# Startgate_Controller_Daughterboard.net
KiCad netlist of a schematic drawn in EAGLE
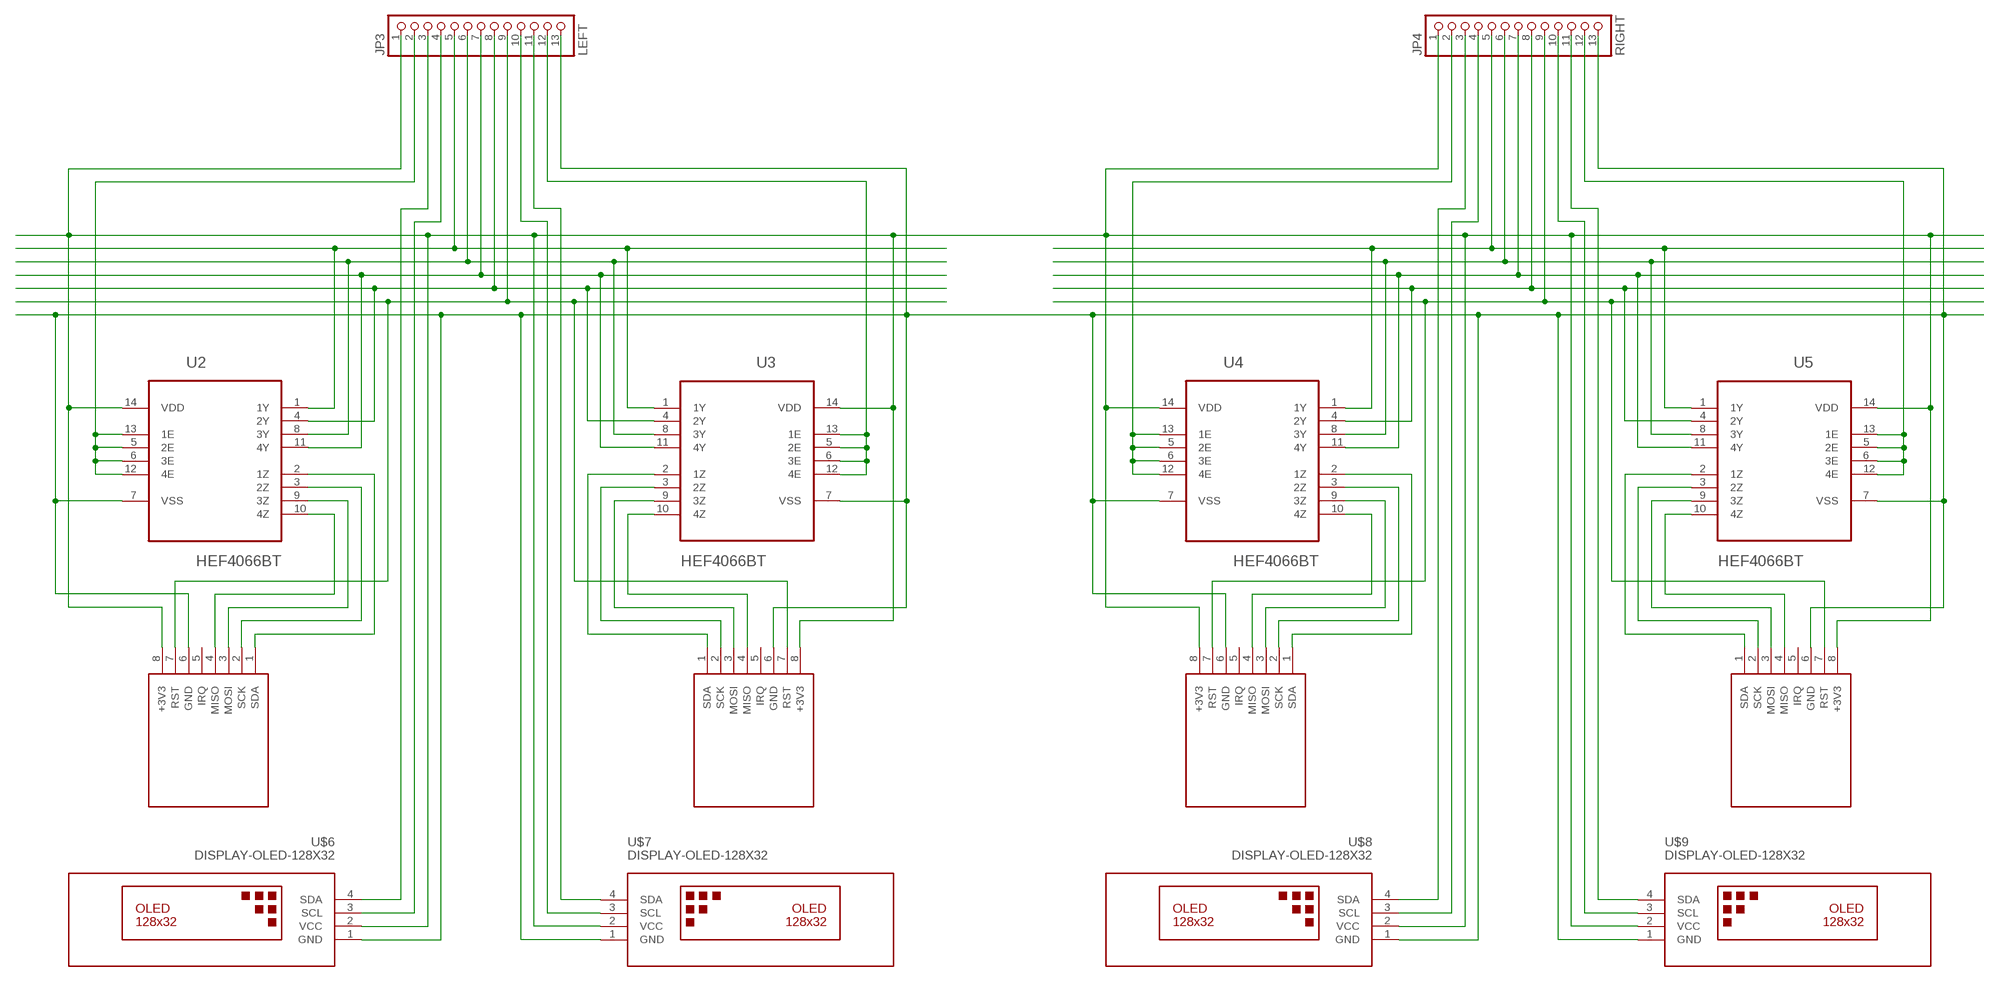
[diagram p0: schematic, sheet 1]

(export (version "E")
  (design (tool "Eeschema 10.0.6"))
  (components
    (comp (ref "JP3")
      (value "LEFT")
      (footprint "eagle-import:1X13")
      (libsource (lib "eagle-import") (part "PINHD-1X13"))
    )
    (comp (ref "JP4")
      (value "RIGHT")
      (footprint "eagle-import:1X13")
      (libsource (lib "eagle-import") (part "PINHD-1X13"))
    )
    (comp (ref "U$2")
      (value "RFID-RC522")
      (footprint "eagle-import:RFID-RC522")
      (libsource (lib "eagle-import") (part "RFID-RC522"))
    )
    (comp (ref "U$3")
      (value "RFID-RC522")
      (footprint "eagle-import:RFID-RC522")
      (libsource (lib "eagle-import") (part "RFID-RC522"))
    )
    (comp (ref "U$4")
      (value "RFID-RC522")
      (footprint "eagle-import:RFID-RC522")
      (libsource (lib "eagle-import") (part "RFID-RC522"))
    )
    (comp (ref "U$5")
      (value "RFID-RC522")
      (footprint "eagle-import:RFID-RC522")
      (libsource (lib "eagle-import") (part "RFID-RC522"))
    )
    (comp (ref "U$6")
      (value "DISPLAY-OLED-128X32")
      (footprint "eagle-import:DISPLAY-OLED-128X32")
      (libsource (lib "eagle-import") (part "DISPLAY-OLED-128X32"))
    )
    (comp (ref "U$7")
      (value "DISPLAY-OLED-128X32")
      (footprint "eagle-import:DISPLAY-OLED-128X32")
      (libsource (lib "eagle-import") (part "DISPLAY-OLED-128X32"))
    )
    (comp (ref "U$8")
      (value "DISPLAY-OLED-128X32")
      (footprint "eagle-import:DISPLAY-OLED-128X32")
      (libsource (lib "eagle-import") (part "DISPLAY-OLED-128X32"))
    )
    (comp (ref "U$9")
      (value "DISPLAY-OLED-128X32")
      (footprint "eagle-import:DISPLAY-OLED-128X32")
      (libsource (lib "eagle-import") (part "DISPLAY-OLED-128X32"))
    )
    (comp (ref "U2")
      (value "HEF4066BT")
      (footprint "eagle-import:SOIC127P600X175-14N")
      (libsource (lib "eagle-import") (part "HEF4066BT"))
    )
    (comp (ref "U3")
      (value "HEF4066BT")
      (footprint "eagle-import:SOIC127P600X175-14N")
      (libsource (lib "eagle-import") (part "HEF4066BT"))
    )
    (comp (ref "U4")
      (value "HEF4066BT")
      (footprint "eagle-import:SOIC127P600X175-14N")
      (libsource (lib "eagle-import") (part "HEF4066BT"))
    )
    (comp (ref "U5")
      (value "HEF4066BT")
      (footprint "eagle-import:SOIC127P600X175-14N")
      (libsource (lib "eagle-import") (part "HEF4066BT"))
    )
  )
  (nets
    (net (code "1") (name "/RST") (class "Default")
      (node (ref "JP3") (pin "9") (pinfunction "9_9") (pintype "passive"))
      (node (ref "JP4") (pin "9") (pinfunction "9_9") (pintype "passive"))
      (node (ref "U$2") (pin "7") (pinfunction "RST_7") (pintype "bidirectional"))
      (node (ref "U$3") (pin "7") (pinfunction "RST_7") (pintype "bidirectional"))
      (node (ref "U$4") (pin "7") (pinfunction "RST_7") (pintype "bidirectional"))
      (node (ref "U$5") (pin "7") (pinfunction "RST_7") (pintype "bidirectional"))
    )
    (net (code "2") (name "Net-(U$2-+3V3)") (class "Default")
      (node (ref "JP3") (pin "1") (pinfunction "1_1") (pintype "passive"))
      (node (ref "JP4") (pin "1") (pinfunction "1_1") (pintype "passive"))
      (node (ref "U$2") (pin "8") (pinfunction "+3V3_8") (pintype "power_in"))
      (node (ref "U$3") (pin "8") (pinfunction "+3V3_8") (pintype "power_in"))
      (node (ref "U$4") (pin "8") (pinfunction "+3V3_8") (pintype "power_in"))
      (node (ref "U$5") (pin "8") (pinfunction "+3V3_8") (pintype "power_in"))
      (node (ref "U$6") (pin "2") (pinfunction "VCC_2") (pintype "power_in"))
      (node (ref "U$7") (pin "2") (pinfunction "VCC_2") (pintype "power_in"))
      (node (ref "U$8") (pin "2") (pinfunction "VCC_2") (pintype "power_in"))
      (node (ref "U$9") (pin "2") (pinfunction "VCC_2") (pintype "power_in"))
      (node (ref "U2") (pin "14") (pinfunction "VDD_14") (pintype "power_in"))
      (node (ref "U3") (pin "14") (pinfunction "VDD_14") (pintype "power_in"))
      (node (ref "U4") (pin "14") (pinfunction "VDD_14") (pintype "power_in"))
      (node (ref "U5") (pin "14") (pinfunction "VDD_14") (pintype "power_in"))
    )
    (net (code "3") (name "Net-(U$2-GND)") (class "Default")
      (node (ref "JP3") (pin "13") (pinfunction "13_13") (pintype "passive"))
      (node (ref "JP4") (pin "13") (pinfunction "13_13") (pintype "passive"))
      (node (ref "U$2") (pin "6") (pinfunction "GND_6") (pintype "power_in"))
      (node (ref "U$3") (pin "6") (pinfunction "GND_6") (pintype "power_in"))
      (node (ref "U$4") (pin "6") (pinfunction "GND_6") (pintype "power_in"))
      (node (ref "U$5") (pin "6") (pinfunction "GND_6") (pintype "power_in"))
      (node (ref "U$6") (pin "1") (pinfunction "GND_1") (pintype "power_in"))
      (node (ref "U$7") (pin "1") (pinfunction "GND_1") (pintype "power_in"))
      (node (ref "U$8") (pin "1") (pinfunction "GND_1") (pintype "power_in"))
      (node (ref "U$9") (pin "1") (pinfunction "GND_1") (pintype "power_in"))
      (node (ref "U2") (pin "7") (pinfunction "VSS_7") (pintype "passive"))
      (node (ref "U3") (pin "7") (pinfunction "VSS_7") (pintype "passive"))
      (node (ref "U4") (pin "7") (pinfunction "VSS_7") (pintype "passive"))
      (node (ref "U5") (pin "7") (pinfunction "VSS_7") (pintype "passive"))
    )
    (net (code "4") (name "Net-(U$2-MISO)") (class "Default")
      (node (ref "U$2") (pin "4") (pinfunction "MISO_4") (pintype "bidirectional"))
      (node (ref "U2") (pin "10") (pinfunction "4Z_10") (pintype "bidirectional"))
    )
    (net (code "5") (name "Net-(U$2-MOSI)") (class "Default")
      (node (ref "U$2") (pin "3") (pinfunction "MOSI_3") (pintype "bidirectional"))
      (node (ref "U2") (pin "9") (pinfunction "3Z_9") (pintype "bidirectional"))
    )
    (net (code "6") (name "Net-(U$2-SCK)") (class "Default")
      (node (ref "U$2") (pin "2") (pinfunction "SCK_2") (pintype "bidirectional"))
      (node (ref "U2") (pin "3") (pinfunction "2Z_3") (pintype "bidirectional"))
    )
    (net (code "7") (name "Net-(U$2-SDA)") (class "Default")
      (node (ref "U$2") (pin "1") (pinfunction "SDA_1") (pintype "bidirectional"))
      (node (ref "U2") (pin "2") (pinfunction "1Z_2") (pintype "bidirectional"))
    )
    (net (code "8") (name "Net-(U$3-MISO)") (class "Default")
      (node (ref "U$3") (pin "4") (pinfunction "MISO_4") (pintype "bidirectional"))
      (node (ref "U3") (pin "10") (pinfunction "4Z_10") (pintype "bidirectional"))
    )
    (net (code "9") (name "Net-(U$3-MOSI)") (class "Default")
      (node (ref "U$3") (pin "3") (pinfunction "MOSI_3") (pintype "bidirectional"))
      (node (ref "U3") (pin "9") (pinfunction "3Z_9") (pintype "bidirectional"))
    )
    (net (code "10") (name "Net-(U$3-SCK)") (class "Default")
      (node (ref "U$3") (pin "2") (pinfunction "SCK_2") (pintype "bidirectional"))
      (node (ref "U3") (pin "3") (pinfunction "2Z_3") (pintype "bidirectional"))
    )
    (net (code "11") (name "Net-(U$3-SDA)") (class "Default")
      (node (ref "U$3") (pin "1") (pinfunction "SDA_1") (pintype "bidirectional"))
      (node (ref "U3") (pin "2") (pinfunction "1Z_2") (pintype "bidirectional"))
    )
    (net (code "12") (name "Net-(U$4-MISO)") (class "Default")
      (node (ref "U$4") (pin "4") (pinfunction "MISO_4") (pintype "bidirectional"))
      (node (ref "U4") (pin "10") (pinfunction "4Z_10") (pintype "bidirectional"))
    )
    (net (code "13") (name "Net-(U$4-MOSI)") (class "Default")
      (node (ref "U$4") (pin "3") (pinfunction "MOSI_3") (pintype "bidirectional"))
      (node (ref "U4") (pin "9") (pinfunction "3Z_9") (pintype "bidirectional"))
    )
    (net (code "14") (name "Net-(U$4-SCK)") (class "Default")
      (node (ref "U$4") (pin "2") (pinfunction "SCK_2") (pintype "bidirectional"))
      (node (ref "U4") (pin "3") (pinfunction "2Z_3") (pintype "bidirectional"))
    )
    (net (code "15") (name "Net-(U$4-SDA)") (class "Default")
      (node (ref "U$4") (pin "1") (pinfunction "SDA_1") (pintype "bidirectional"))
      (node (ref "U4") (pin "2") (pinfunction "1Z_2") (pintype "bidirectional"))
    )
    (net (code "16") (name "Net-(U$5-MISO)") (class "Default")
      (node (ref "U$5") (pin "4") (pinfunction "MISO_4") (pintype "bidirectional"))
      (node (ref "U5") (pin "10") (pinfunction "4Z_10") (pintype "bidirectional"))
    )
    (net (code "17") (name "Net-(U$5-MOSI)") (class "Default")
      (node (ref "U$5") (pin "3") (pinfunction "MOSI_3") (pintype "bidirectional"))
      (node (ref "U5") (pin "9") (pinfunction "3Z_9") (pintype "bidirectional"))
    )
    (net (code "18") (name "Net-(U$5-SCK)") (class "Default")
      (node (ref "U$5") (pin "2") (pinfunction "SCK_2") (pintype "bidirectional"))
      (node (ref "U5") (pin "3") (pinfunction "2Z_3") (pintype "bidirectional"))
    )
    (net (code "19") (name "Net-(U$5-SDA)") (class "Default")
      (node (ref "U$5") (pin "1") (pinfunction "SDA_1") (pintype "bidirectional"))
      (node (ref "U5") (pin "2") (pinfunction "1Z_2") (pintype "bidirectional"))
    )
    (net (code "20") (name "Net-(U$6-SCL)") (class "Default")
      (node (ref "JP3") (pin "4") (pinfunction "4_4") (pintype "passive"))
      (node (ref "U$6") (pin "3") (pinfunction "SCL_3") (pintype "bidirectional"))
    )
    (net (code "21") (name "Net-(U$6-SDA)") (class "Default")
      (node (ref "JP3") (pin "3") (pinfunction "3_3") (pintype "passive"))
      (node (ref "U$6") (pin "4") (pinfunction "SDA_4") (pintype "bidirectional"))
    )
    (net (code "22") (name "Net-(U$7-SCL)") (class "Default")
      (node (ref "JP3") (pin "10") (pinfunction "10_10") (pintype "passive"))
      (node (ref "U$7") (pin "3") (pinfunction "SCL_3") (pintype "bidirectional"))
    )
    (net (code "23") (name "Net-(U$7-SDA)") (class "Default")
      (node (ref "JP3") (pin "11") (pinfunction "11_11") (pintype "passive"))
      (node (ref "U$7") (pin "4") (pinfunction "SDA_4") (pintype "bidirectional"))
    )
    (net (code "24") (name "Net-(U$8-SCL)") (class "Default")
      (node (ref "JP4") (pin "4") (pinfunction "4_4") (pintype "passive"))
      (node (ref "U$8") (pin "3") (pinfunction "SCL_3") (pintype "bidirectional"))
    )
    (net (code "25") (name "Net-(U$8-SDA)") (class "Default")
      (node (ref "JP4") (pin "3") (pinfunction "3_3") (pintype "passive"))
      (node (ref "U$8") (pin "4") (pinfunction "SDA_4") (pintype "bidirectional"))
    )
    (net (code "26") (name "Net-(U$9-SCL)") (class "Default")
      (node (ref "JP4") (pin "10") (pinfunction "10_10") (pintype "passive"))
      (node (ref "U$9") (pin "3") (pinfunction "SCL_3") (pintype "bidirectional"))
    )
    (net (code "27") (name "Net-(U$9-SDA)") (class "Default")
      (node (ref "JP4") (pin "11") (pinfunction "11_11") (pintype "passive"))
      (node (ref "U$9") (pin "4") (pinfunction "SDA_4") (pintype "bidirectional"))
    )
    (net (code "28") (name "Net-(U2-1E)") (class "Default")
      (node (ref "JP3") (pin "2") (pinfunction "2_2") (pintype "passive"))
      (node (ref "U2") (pin "12") (pinfunction "4E_12") (pintype "input"))
      (node (ref "U2") (pin "13") (pinfunction "1E_13") (pintype "input"))
      (node (ref "U2") (pin "5") (pinfunction "2E_5") (pintype "input"))
      (node (ref "U2") (pin "6") (pinfunction "3E_6") (pintype "input"))
    )
    (net (code "29") (name "Net-(U2-1Y)") (class "Default")
      (node (ref "JP3") (pin "5") (pinfunction "5_5") (pintype "passive"))
      (node (ref "U2") (pin "1") (pinfunction "1Y_1") (pintype "bidirectional"))
      (node (ref "U3") (pin "1") (pinfunction "1Y_1") (pintype "bidirectional"))
    )
    (net (code "30") (name "Net-(U2-2Y)") (class "Default")
      (node (ref "JP3") (pin "8") (pinfunction "8_8") (pintype "passive"))
      (node (ref "U2") (pin "4") (pinfunction "2Y_4") (pintype "bidirectional"))
      (node (ref "U3") (pin "4") (pinfunction "2Y_4") (pintype "bidirectional"))
    )
    (net (code "31") (name "Net-(U2-3Y)") (class "Default")
      (node (ref "JP3") (pin "6") (pinfunction "6_6") (pintype "passive"))
      (node (ref "U2") (pin "8") (pinfunction "3Y_8") (pintype "bidirectional"))
      (node (ref "U3") (pin "8") (pinfunction "3Y_8") (pintype "bidirectional"))
    )
    (net (code "32") (name "Net-(U2-4Y)") (class "Default")
      (node (ref "JP3") (pin "7") (pinfunction "7_7") (pintype "passive"))
      (node (ref "U2") (pin "11") (pinfunction "4Y_11") (pintype "bidirectional"))
      (node (ref "U3") (pin "11") (pinfunction "4Y_11") (pintype "bidirectional"))
    )
    (net (code "33") (name "Net-(U3-1E)") (class "Default")
      (node (ref "JP3") (pin "12") (pinfunction "12_12") (pintype "passive"))
      (node (ref "U3") (pin "12") (pinfunction "4E_12") (pintype "input"))
      (node (ref "U3") (pin "13") (pinfunction "1E_13") (pintype "input"))
      (node (ref "U3") (pin "5") (pinfunction "2E_5") (pintype "input"))
      (node (ref "U3") (pin "6") (pinfunction "3E_6") (pintype "input"))
    )
    (net (code "34") (name "Net-(U4-1E)") (class "Default")
      (node (ref "JP4") (pin "2") (pinfunction "2_2") (pintype "passive"))
      (node (ref "U4") (pin "12") (pinfunction "4E_12") (pintype "input"))
      (node (ref "U4") (pin "13") (pinfunction "1E_13") (pintype "input"))
      (node (ref "U4") (pin "5") (pinfunction "2E_5") (pintype "input"))
      (node (ref "U4") (pin "6") (pinfunction "3E_6") (pintype "input"))
    )
    (net (code "35") (name "Net-(U4-1Y)") (class "Default")
      (node (ref "JP4") (pin "5") (pinfunction "5_5") (pintype "passive"))
      (node (ref "U4") (pin "1") (pinfunction "1Y_1") (pintype "bidirectional"))
      (node (ref "U5") (pin "1") (pinfunction "1Y_1") (pintype "bidirectional"))
    )
    (net (code "36") (name "Net-(U4-2Y)") (class "Default")
      (node (ref "JP4") (pin "8") (pinfunction "8_8") (pintype "passive"))
      (node (ref "U4") (pin "4") (pinfunction "2Y_4") (pintype "bidirectional"))
      (node (ref "U5") (pin "4") (pinfunction "2Y_4") (pintype "bidirectional"))
    )
    (net (code "37") (name "Net-(U4-3Y)") (class "Default")
      (node (ref "JP4") (pin "6") (pinfunction "6_6") (pintype "passive"))
      (node (ref "U4") (pin "8") (pinfunction "3Y_8") (pintype "bidirectional"))
      (node (ref "U5") (pin "8") (pinfunction "3Y_8") (pintype "bidirectional"))
    )
    (net (code "38") (name "Net-(U4-4Y)") (class "Default")
      (node (ref "JP4") (pin "7") (pinfunction "7_7") (pintype "passive"))
      (node (ref "U4") (pin "11") (pinfunction "4Y_11") (pintype "bidirectional"))
      (node (ref "U5") (pin "11") (pinfunction "4Y_11") (pintype "bidirectional"))
    )
    (net (code "39") (name "Net-(U5-1E)") (class "Default")
      (node (ref "JP4") (pin "12") (pinfunction "12_12") (pintype "passive"))
      (node (ref "U5") (pin "12") (pinfunction "4E_12") (pintype "input"))
      (node (ref "U5") (pin "13") (pinfunction "1E_13") (pintype "input"))
      (node (ref "U5") (pin "5") (pinfunction "2E_5") (pintype "input"))
      (node (ref "U5") (pin "6") (pinfunction "3E_6") (pintype "input"))
    )
    (net (code "40") (name "unconnected-(U$2-IRQ-Pad5)") (class "Default")
      (node (ref "U$2") (pin "5") (pinfunction "IRQ_5") (pintype "bidirectional"))
    )
    (net (code "41") (name "unconnected-(U$3-IRQ-Pad5)") (class "Default")
      (node (ref "U$3") (pin "5") (pinfunction "IRQ_5") (pintype "bidirectional"))
    )
    (net (code "42") (name "unconnected-(U$4-IRQ-Pad5)") (class "Default")
      (node (ref "U$4") (pin "5") (pinfunction "IRQ_5") (pintype "bidirectional"))
    )
    (net (code "43") (name "unconnected-(U$5-IRQ-Pad5)") (class "Default")
      (node (ref "U$5") (pin "5") (pinfunction "IRQ_5") (pintype "bidirectional"))
    )
  )
)
